# FPGA1.net
KiCad netlist of a schematic drawn in Altium Designer
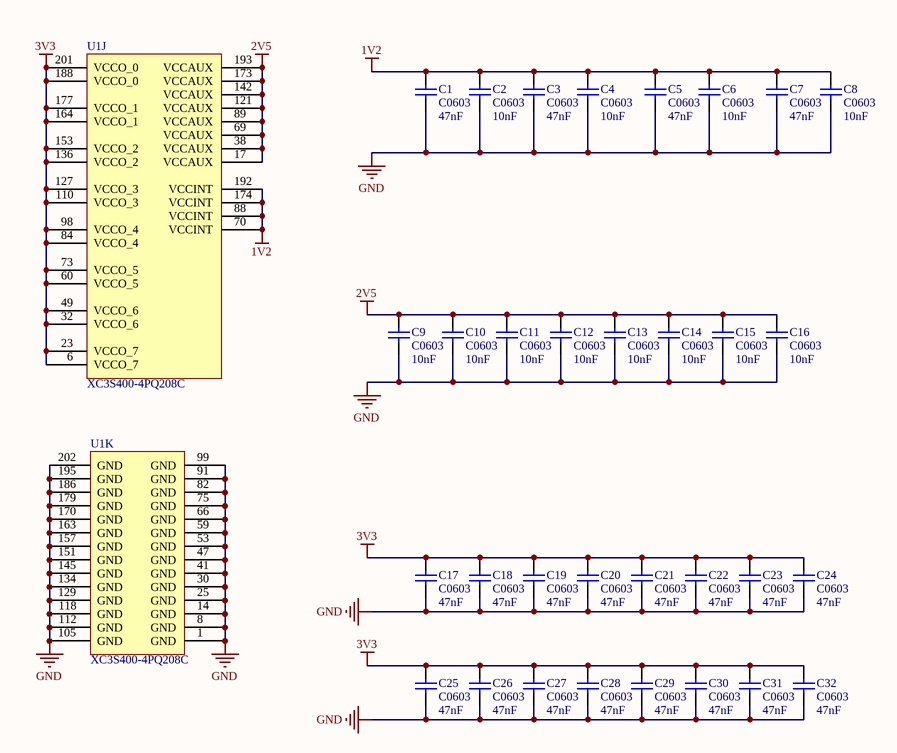
[diagram p0: FPGA1.SchDoc]

(export (version "E")
  (design (tool "Eeschema 10.0.6"))
  (components
    (comp (ref "C1")
      (value "C0603")
      (footprint "0603")
      (description "Ceramic Chip Capacitor - Standard")
      (fields (field (name "ALTIUM_VALUE") "47nF") (field (name "PUBLISHER") "Altium Limited"))
      (libsource (lib "KEMET Chip Capacitor") (part "C0603"))
    )
    (comp (ref "C2")
      (value "C0603")
      (footprint "0603")
      (description "Ceramic Chip Capacitor - Standard")
      (fields (field (name "ALTIUM_VALUE") "10nF") (field (name "PUBLISHER") "Altium Limited"))
      (libsource (lib "KEMET Chip Capacitor") (part "C0603"))
    )
    (comp (ref "C3")
      (value "C0603")
      (footprint "0603")
      (description "Ceramic Chip Capacitor - Standard")
      (fields (field (name "ALTIUM_VALUE") "47nF") (field (name "PUBLISHER") "Altium Limited"))
      (libsource (lib "KEMET Chip Capacitor") (part "C0603"))
    )
    (comp (ref "C4")
      (value "C0603")
      (footprint "0603")
      (description "Ceramic Chip Capacitor - Standard")
      (fields (field (name "ALTIUM_VALUE") "10nF") (field (name "PUBLISHER") "Altium Limited"))
      (libsource (lib "KEMET Chip Capacitor") (part "C0603"))
    )
    (comp (ref "C5")
      (value "C0603")
      (footprint "0603")
      (description "Ceramic Chip Capacitor - Standard")
      (fields (field (name "ALTIUM_VALUE") "47nF") (field (name "PUBLISHER") "Altium Limited"))
      (libsource (lib "KEMET Chip Capacitor") (part "C0603"))
    )
    (comp (ref "C6")
      (value "C0603")
      (footprint "0603")
      (description "Ceramic Chip Capacitor - Standard")
      (fields (field (name "ALTIUM_VALUE") "10nF") (field (name "PUBLISHER") "Altium Limited"))
      (libsource (lib "KEMET Chip Capacitor") (part "C0603"))
    )
    (comp (ref "C7")
      (value "C0603")
      (footprint "0603")
      (description "Ceramic Chip Capacitor - Standard")
      (fields (field (name "ALTIUM_VALUE") "47nF") (field (name "PUBLISHER") "Altium Limited"))
      (libsource (lib "KEMET Chip Capacitor") (part "C0603"))
    )
    (comp (ref "C8")
      (value "C0603")
      (footprint "0603")
      (description "Ceramic Chip Capacitor - Standard")
      (fields (field (name "ALTIUM_VALUE") "10nF") (field (name "PUBLISHER") "Altium Limited"))
      (libsource (lib "KEMET Chip Capacitor") (part "C0603"))
    )
    (comp (ref "C9")
      (value "C0603")
      (footprint "0603")
      (description "Ceramic Chip Capacitor - Standard")
      (fields (field (name "ALTIUM_VALUE") "10nF") (field (name "PUBLISHER") "Altium Limited"))
      (libsource (lib "KEMET Chip Capacitor") (part "C0603"))
    )
    (comp (ref "C10")
      (value "C0603")
      (footprint "0603")
      (description "Ceramic Chip Capacitor - Standard")
      (fields (field (name "ALTIUM_VALUE") "10nF") (field (name "PUBLISHER") "Altium Limited"))
      (libsource (lib "KEMET Chip Capacitor") (part "C0603"))
    )
    (comp (ref "C11")
      (value "C0603")
      (footprint "0603")
      (description "Ceramic Chip Capacitor - Standard")
      (fields (field (name "ALTIUM_VALUE") "10nF") (field (name "PUBLISHER") "Altium Limited"))
      (libsource (lib "KEMET Chip Capacitor") (part "C0603"))
    )
    (comp (ref "C12")
      (value "C0603")
      (footprint "0603")
      (description "Ceramic Chip Capacitor - Standard")
      (fields (field (name "ALTIUM_VALUE") "10nF") (field (name "PUBLISHER") "Altium Limited"))
      (libsource (lib "KEMET Chip Capacitor") (part "C0603"))
    )
    (comp (ref "C13")
      (value "C0603")
      (footprint "0603")
      (description "Ceramic Chip Capacitor - Standard")
      (fields (field (name "ALTIUM_VALUE") "10nF") (field (name "PUBLISHER") "Altium Limited"))
      (libsource (lib "KEMET Chip Capacitor") (part "C0603"))
    )
    (comp (ref "C14")
      (value "C0603")
      (footprint "0603")
      (description "Ceramic Chip Capacitor - Standard")
      (fields (field (name "ALTIUM_VALUE") "10nF") (field (name "PUBLISHER") "Altium Limited"))
      (libsource (lib "KEMET Chip Capacitor") (part "C0603"))
    )
    (comp (ref "C15")
      (value "C0603")
      (footprint "0603")
      (description "Ceramic Chip Capacitor - Standard")
      (fields (field (name "ALTIUM_VALUE") "10nF") (field (name "PUBLISHER") "Altium Limited"))
      (libsource (lib "KEMET Chip Capacitor") (part "C0603"))
    )
    (comp (ref "C16")
      (value "C0603")
      (footprint "0603")
      (description "Ceramic Chip Capacitor - Standard")
      (fields (field (name "ALTIUM_VALUE") "10nF") (field (name "PUBLISHER") "Altium Limited"))
      (libsource (lib "KEMET Chip Capacitor") (part "C0603"))
    )
    (comp (ref "C17")
      (value "C0603")
      (footprint "0603")
      (description "Ceramic Chip Capacitor - Standard")
      (fields (field (name "ALTIUM_VALUE") "47nF") (field (name "PUBLISHER") "Altium Limited"))
      (libsource (lib "KEMET Chip Capacitor") (part "C0603"))
    )
    (comp (ref "C18")
      (value "C0603")
      (footprint "0603")
      (description "Ceramic Chip Capacitor - Standard")
      (fields (field (name "ALTIUM_VALUE") "47nF") (field (name "PUBLISHER") "Altium Limited"))
      (libsource (lib "KEMET Chip Capacitor") (part "C0603"))
    )
    (comp (ref "C19")
      (value "C0603")
      (footprint "0603")
      (description "Ceramic Chip Capacitor - Standard")
      (fields (field (name "ALTIUM_VALUE") "47nF") (field (name "PUBLISHER") "Altium Limited"))
      (libsource (lib "KEMET Chip Capacitor") (part "C0603"))
    )
    (comp (ref "C20")
      (value "C0603")
      (footprint "0603")
      (description "Ceramic Chip Capacitor - Standard")
      (fields (field (name "ALTIUM_VALUE") "47nF") (field (name "PUBLISHER") "Altium Limited"))
      (libsource (lib "KEMET Chip Capacitor") (part "C0603"))
    )
    (comp (ref "C21")
      (value "C0603")
      (footprint "0603")
      (description "Ceramic Chip Capacitor - Standard")
      (fields (field (name "ALTIUM_VALUE") "47nF") (field (name "PUBLISHER") "Altium Limited"))
      (libsource (lib "KEMET Chip Capacitor") (part "C0603"))
    )
    (comp (ref "C22")
      (value "C0603")
      (footprint "0603")
      (description "Ceramic Chip Capacitor - Standard")
      (fields (field (name "ALTIUM_VALUE") "47nF") (field (name "PUBLISHER") "Altium Limited"))
      (libsource (lib "KEMET Chip Capacitor") (part "C0603"))
    )
    (comp (ref "C23")
      (value "C0603")
      (footprint "0603")
      (description "Ceramic Chip Capacitor - Standard")
      (fields (field (name "ALTIUM_VALUE") "47nF") (field (name "PUBLISHER") "Altium Limited"))
      (libsource (lib "KEMET Chip Capacitor") (part "C0603"))
    )
    (comp (ref "C24")
      (value "C0603")
      (footprint "0603")
      (description "Ceramic Chip Capacitor - Standard")
      (fields (field (name "ALTIUM_VALUE") "47nF") (field (name "PUBLISHER") "Altium Limited"))
      (libsource (lib "KEMET Chip Capacitor") (part "C0603"))
    )
    (comp (ref "C25")
      (value "C0603")
      (footprint "0603")
      (description "Ceramic Chip Capacitor - Standard")
      (fields (field (name "ALTIUM_VALUE") "47nF") (field (name "PUBLISHER") "Altium Limited"))
      (libsource (lib "KEMET Chip Capacitor") (part "C0603"))
    )
    (comp (ref "C26")
      (value "C0603")
      (footprint "0603")
      (description "Ceramic Chip Capacitor - Standard")
      (fields (field (name "ALTIUM_VALUE") "47nF") (field (name "PUBLISHER") "Altium Limited"))
      (libsource (lib "KEMET Chip Capacitor") (part "C0603"))
    )
    (comp (ref "C27")
      (value "C0603")
      (footprint "0603")
      (description "Ceramic Chip Capacitor - Standard")
      (fields (field (name "ALTIUM_VALUE") "47nF") (field (name "PUBLISHER") "Altium Limited"))
      (libsource (lib "KEMET Chip Capacitor") (part "C0603"))
    )
    (comp (ref "C28")
      (value "C0603")
      (footprint "0603")
      (description "Ceramic Chip Capacitor - Standard")
      (fields (field (name "ALTIUM_VALUE") "47nF") (field (name "PUBLISHER") "Altium Limited"))
      (libsource (lib "KEMET Chip Capacitor") (part "C0603"))
    )
    (comp (ref "C29")
      (value "C0603")
      (footprint "0603")
      (description "Ceramic Chip Capacitor - Standard")
      (fields (field (name "ALTIUM_VALUE") "47nF") (field (name "PUBLISHER") "Altium Limited"))
      (libsource (lib "KEMET Chip Capacitor") (part "C0603"))
    )
    (comp (ref "C30")
      (value "C0603")
      (footprint "0603")
      (description "Ceramic Chip Capacitor - Standard")
      (fields (field (name "ALTIUM_VALUE") "47nF") (field (name "PUBLISHER") "Altium Limited"))
      (libsource (lib "KEMET Chip Capacitor") (part "C0603"))
    )
    (comp (ref "C31")
      (value "C0603")
      (footprint "0603")
      (description "Ceramic Chip Capacitor - Standard")
      (fields (field (name "ALTIUM_VALUE") "47nF") (field (name "PUBLISHER") "Altium Limited"))
      (libsource (lib "KEMET Chip Capacitor") (part "C0603"))
    )
    (comp (ref "C32")
      (value "C0603")
      (footprint "0603")
      (description "Ceramic Chip Capacitor - Standard")
      (fields (field (name "ALTIUM_VALUE") "47nF") (field (name "PUBLISHER") "Altium Limited"))
      (libsource (lib "KEMET Chip Capacitor") (part "C0603"))
    )
    (comp (ref "U1")
      (value "XC3S400-4PQ208C")
      (footprint "PQ208_N")
      (description "Spartan-3 1.2V FPGA, 141 User I/Os, 208-Pin PQFP, Standard Performance, Commercial Grade")
      (libsource (lib "Xilinx Spartan-3") (part "XC3S400-4PQ208C"))
    )
  )
  (nets
    (net (code "1") (name "1V2") (class "Default")
      (node (ref "C1") (pin "2") (pinfunction "2_2") (pintype "passive"))
      (node (ref "C2") (pin "2") (pinfunction "2_2") (pintype "passive"))
      (node (ref "C3") (pin "2") (pinfunction "2_2") (pintype "passive"))
      (node (ref "C4") (pin "2") (pinfunction "2_2") (pintype "passive"))
      (node (ref "C5") (pin "2") (pinfunction "2_2") (pintype "passive"))
      (node (ref "C6") (pin "2") (pinfunction "2_2") (pintype "passive"))
      (node (ref "C7") (pin "2") (pinfunction "2_2") (pintype "passive"))
      (node (ref "C8") (pin "2") (pinfunction "2_2") (pintype "passive"))
      (node (ref "U1") (pin "174") (pinfunction "VCCINT_174") (pintype "power_in"))
      (node (ref "U1") (pin "192") (pinfunction "VCCINT_192") (pintype "power_in"))
      (node (ref "U1") (pin "70") (pinfunction "VCCINT_70") (pintype "power_in"))
      (node (ref "U1") (pin "88") (pinfunction "VCCINT_88") (pintype "power_in"))
    )
    (net (code "2") (name "2V5") (class "Default")
      (node (ref "C10") (pin "2") (pinfunction "2_2") (pintype "passive"))
      (node (ref "C11") (pin "2") (pinfunction "2_2") (pintype "passive"))
      (node (ref "C12") (pin "2") (pinfunction "2_2") (pintype "passive"))
      (node (ref "C13") (pin "2") (pinfunction "2_2") (pintype "passive"))
      (node (ref "C14") (pin "2") (pinfunction "2_2") (pintype "passive"))
      (node (ref "C15") (pin "2") (pinfunction "2_2") (pintype "passive"))
      (node (ref "C16") (pin "2") (pinfunction "2_2") (pintype "passive"))
      (node (ref "C9") (pin "2") (pinfunction "2_2") (pintype "passive"))
      (node (ref "U1") (pin "121") (pinfunction "VCCAUX_121") (pintype "power_in"))
      (node (ref "U1") (pin "142") (pinfunction "VCCAUX_142") (pintype "power_in"))
      (node (ref "U1") (pin "17") (pinfunction "VCCAUX_17") (pintype "power_in"))
      (node (ref "U1") (pin "173") (pinfunction "VCCAUX_173") (pintype "power_in"))
      (node (ref "U1") (pin "193") (pinfunction "VCCAUX_193") (pintype "power_in"))
      (node (ref "U1") (pin "38") (pinfunction "VCCAUX_38") (pintype "power_in"))
      (node (ref "U1") (pin "69") (pinfunction "VCCAUX_69") (pintype "power_in"))
      (node (ref "U1") (pin "89") (pinfunction "VCCAUX_89") (pintype "power_in"))
    )
    (net (code "3") (name "3V3") (class "Default")
      (node (ref "C17") (pin "2") (pinfunction "2_2") (pintype "passive"))
      (node (ref "C18") (pin "2") (pinfunction "2_2") (pintype "passive"))
      (node (ref "C19") (pin "2") (pinfunction "2_2") (pintype "passive"))
      (node (ref "C20") (pin "2") (pinfunction "2_2") (pintype "passive"))
      (node (ref "C21") (pin "2") (pinfunction "2_2") (pintype "passive"))
      (node (ref "C22") (pin "2") (pinfunction "2_2") (pintype "passive"))
      (node (ref "C23") (pin "2") (pinfunction "2_2") (pintype "passive"))
      (node (ref "C24") (pin "2") (pinfunction "2_2") (pintype "passive"))
      (node (ref "C25") (pin "2") (pinfunction "2_2") (pintype "passive"))
      (node (ref "C26") (pin "2") (pinfunction "2_2") (pintype "passive"))
      (node (ref "C27") (pin "2") (pinfunction "2_2") (pintype "passive"))
      (node (ref "C28") (pin "2") (pinfunction "2_2") (pintype "passive"))
      (node (ref "C29") (pin "2") (pinfunction "2_2") (pintype "passive"))
      (node (ref "C30") (pin "2") (pinfunction "2_2") (pintype "passive"))
      (node (ref "C31") (pin "2") (pinfunction "2_2") (pintype "passive"))
      (node (ref "C32") (pin "2") (pinfunction "2_2") (pintype "passive"))
      (node (ref "U1") (pin "110") (pinfunction "VCCO_3_110") (pintype "power_in"))
      (node (ref "U1") (pin "127") (pinfunction "VCCO_3_127") (pintype "power_in"))
      (node (ref "U1") (pin "136") (pinfunction "VCCO_2_136") (pintype "power_in"))
      (node (ref "U1") (pin "153") (pinfunction "VCCO_2_153") (pintype "power_in"))
      (node (ref "U1") (pin "164") (pinfunction "VCCO_1_164") (pintype "power_in"))
      (node (ref "U1") (pin "177") (pinfunction "VCCO_1_177") (pintype "power_in"))
      (node (ref "U1") (pin "188") (pinfunction "VCCO_0_188") (pintype "power_in"))
      (node (ref "U1") (pin "201") (pinfunction "VCCO_0_201") (pintype "power_in"))
      (node (ref "U1") (pin "23") (pinfunction "VCCO_7_23") (pintype "power_in"))
      (node (ref "U1") (pin "32") (pinfunction "VCCO_6_32") (pintype "power_in"))
      (node (ref "U1") (pin "49") (pinfunction "VCCO_6_49") (pintype "power_in"))
      (node (ref "U1") (pin "6") (pinfunction "VCCO_7_6") (pintype "power_in"))
      (node (ref "U1") (pin "60") (pinfunction "VCCO_5_60") (pintype "power_in"))
      (node (ref "U1") (pin "73") (pinfunction "VCCO_5_73") (pintype "power_in"))
      (node (ref "U1") (pin "84") (pinfunction "VCCO_4_84") (pintype "power_in"))
      (node (ref "U1") (pin "98") (pinfunction "VCCO_4_98") (pintype "power_in"))
    )
    (net (code "4") (name "GND") (class "Default")
      (node (ref "C1") (pin "1") (pinfunction "1_1") (pintype "passive"))
      (node (ref "C10") (pin "1") (pinfunction "1_1") (pintype "passive"))
      (node (ref "C11") (pin "1") (pinfunction "1_1") (pintype "passive"))
      (node (ref "C12") (pin "1") (pinfunction "1_1") (pintype "passive"))
      (node (ref "C13") (pin "1") (pinfunction "1_1") (pintype "passive"))
      (node (ref "C14") (pin "1") (pinfunction "1_1") (pintype "passive"))
      (node (ref "C15") (pin "1") (pinfunction "1_1") (pintype "passive"))
      (node (ref "C16") (pin "1") (pinfunction "1_1") (pintype "passive"))
      (node (ref "C17") (pin "1") (pinfunction "1_1") (pintype "passive"))
      (node (ref "C18") (pin "1") (pinfunction "1_1") (pintype "passive"))
      (node (ref "C19") (pin "1") (pinfunction "1_1") (pintype "passive"))
      (node (ref "C2") (pin "1") (pinfunction "1_1") (pintype "passive"))
      (node (ref "C20") (pin "1") (pinfunction "1_1") (pintype "passive"))
      (node (ref "C21") (pin "1") (pinfunction "1_1") (pintype "passive"))
      (node (ref "C22") (pin "1") (pinfunction "1_1") (pintype "passive"))
      (node (ref "C23") (pin "1") (pinfunction "1_1") (pintype "passive"))
      (node (ref "C24") (pin "1") (pinfunction "1_1") (pintype "passive"))
      (node (ref "C25") (pin "1") (pinfunction "1_1") (pintype "passive"))
      (node (ref "C26") (pin "1") (pinfunction "1_1") (pintype "passive"))
      (node (ref "C27") (pin "1") (pinfunction "1_1") (pintype "passive"))
      (node (ref "C28") (pin "1") (pinfunction "1_1") (pintype "passive"))
      (node (ref "C29") (pin "1") (pinfunction "1_1") (pintype "passive"))
      (node (ref "C3") (pin "1") (pinfunction "1_1") (pintype "passive"))
      (node (ref "C30") (pin "1") (pinfunction "1_1") (pintype "passive"))
      (node (ref "C31") (pin "1") (pinfunction "1_1") (pintype "passive"))
      (node (ref "C32") (pin "1") (pinfunction "1_1") (pintype "passive"))
      (node (ref "C4") (pin "1") (pinfunction "1_1") (pintype "passive"))
      (node (ref "C5") (pin "1") (pinfunction "1_1") (pintype "passive"))
      (node (ref "C6") (pin "1") (pinfunction "1_1") (pintype "passive"))
      (node (ref "C7") (pin "1") (pinfunction "1_1") (pintype "passive"))
      (node (ref "C8") (pin "1") (pinfunction "1_1") (pintype "passive"))
      (node (ref "C9") (pin "1") (pinfunction "1_1") (pintype "passive"))
      (node (ref "U1") (pin "1") (pinfunction "GND_1") (pintype "power_in"))
      (node (ref "U1") (pin "105") (pinfunction "GND_105") (pintype "power_in"))
      (node (ref "U1") (pin "112") (pinfunction "GND_112") (pintype "power_in"))
      (node (ref "U1") (pin "118") (pinfunction "GND_118") (pintype "power_in"))
      (node (ref "U1") (pin "129") (pinfunction "GND_129") (pintype "power_in"))
      (node (ref "U1") (pin "134") (pinfunction "GND_134") (pintype "power_in"))
      (node (ref "U1") (pin "14") (pinfunction "GND_14") (pintype "power_in"))
      (node (ref "U1") (pin "145") (pinfunction "GND_145") (pintype "power_in"))
      (node (ref "U1") (pin "151") (pinfunction "GND_151") (pintype "power_in"))
      (node (ref "U1") (pin "157") (pinfunction "GND_157") (pintype "power_in"))
      (node (ref "U1") (pin "163") (pinfunction "GND_163") (pintype "power_in"))
      (node (ref "U1") (pin "170") (pinfunction "GND_170") (pintype "power_in"))
      (node (ref "U1") (pin "179") (pinfunction "GND_179") (pintype "power_in"))
      (node (ref "U1") (pin "186") (pinfunction "GND_186") (pintype "power_in"))
      (node (ref "U1") (pin "195") (pinfunction "GND_195") (pintype "power_in"))
      (node (ref "U1") (pin "202") (pinfunction "GND_202") (pintype "power_in"))
      (node (ref "U1") (pin "25") (pinfunction "GND_25") (pintype "power_in"))
      (node (ref "U1") (pin "30") (pinfunction "GND_30") (pintype "power_in"))
      (node (ref "U1") (pin "41") (pinfunction "GND_41") (pintype "power_in"))
      (node (ref "U1") (pin "47") (pinfunction "GND_47") (pintype "power_in"))
      (node (ref "U1") (pin "53") (pinfunction "GND_53") (pintype "power_in"))
      (node (ref "U1") (pin "59") (pinfunction "GND_59") (pintype "power_in"))
      (node (ref "U1") (pin "66") (pinfunction "GND_66") (pintype "power_in"))
      (node (ref "U1") (pin "75") (pinfunction "GND_75") (pintype "power_in"))
      (node (ref "U1") (pin "8") (pinfunction "GND_8") (pintype "power_in"))
      (node (ref "U1") (pin "82") (pinfunction "GND_82") (pintype "power_in"))
      (node (ref "U1") (pin "91") (pinfunction "GND_91") (pintype "power_in"))
      (node (ref "U1") (pin "99") (pinfunction "GND_99") (pintype "power_in"))
    )
  )
)
